# Sheet13.net
KiCad netlist of a schematic drawn in Altium Designer
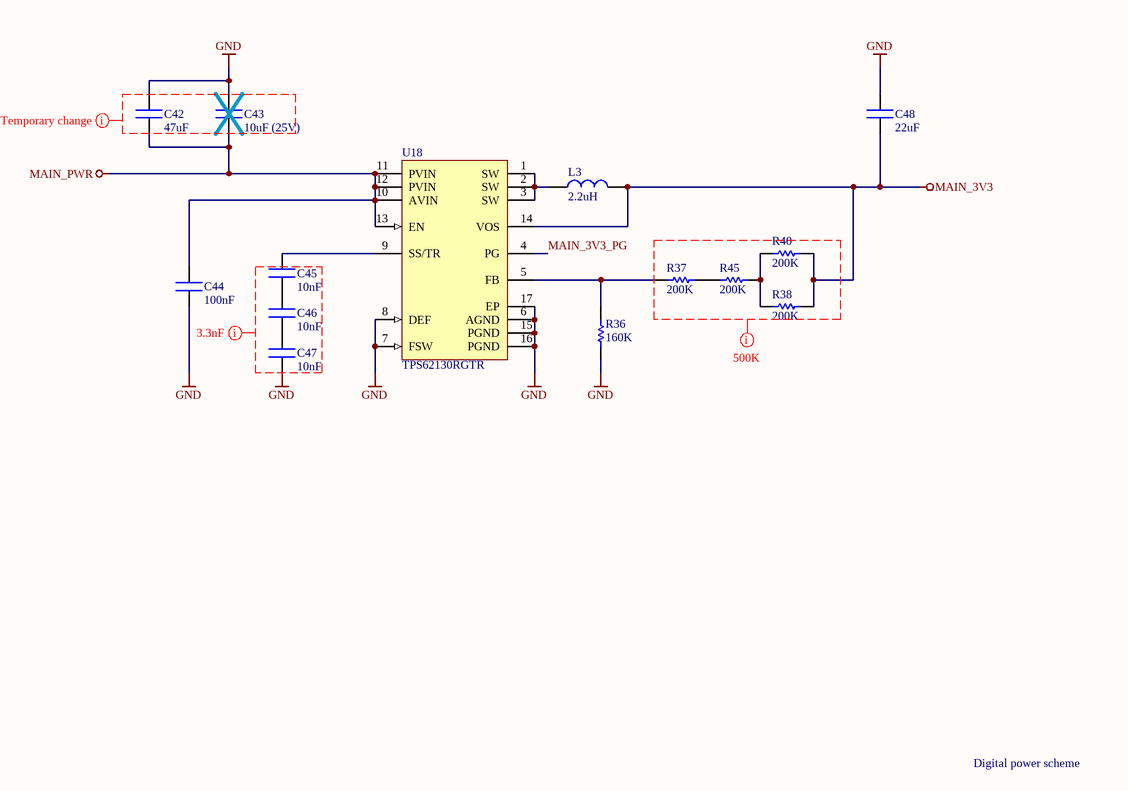
[diagram p0: Sheet13.SchDoc]

(export (version "E")
  (design (tool "Eeschema 10.0.6"))
  (components
    (comp (ref "C42")
      (value "47uF")
      (footprint "CAPC2012X12N")
      (description "Ceramic Chip Capacitor")
      (libsource (lib "Integrated_Library") (part "C0805"))
    )
    (comp (ref "C43")
      (value "10uF (25V)")
      (footprint "CAPC3216X16N")
      (description "Ceramic Chip Capacitor")
      (libsource (lib "Integrated_Library") (part "C1206"))
    )
    (comp (ref "C44")
      (value "100nF")
      (footprint "CAPC1608X08N")
      (description "Ceramic Chip Capacitor")
      (libsource (lib "Integrated_Library") (part "C0603"))
    )
    (comp (ref "C45")
      (value "10nF")
      (footprint "CAPC1005X05N")
      (description "Ceramic Chip Capacitor")
      (libsource (lib "Integrated_Library") (part "C0402"))
    )
    (comp (ref "C46")
      (value "10nF")
      (footprint "CAPC1005X05N")
      (description "Ceramic Chip Capacitor")
      (libsource (lib "Integrated_Library") (part "C0402"))
    )
    (comp (ref "C47")
      (value "10nF")
      (footprint "CAPC1005X05N")
      (description "Ceramic Chip Capacitor")
      (libsource (lib "Integrated_Library") (part "C0402"))
    )
    (comp (ref "C48")
      (value "22uF")
      (footprint "CAPC1608X08N")
      (description "Ceramic Chip Capacitor")
      (libsource (lib "Integrated_Library") (part "C0603"))
    )
    (comp (ref "L3")
      (value "2.2uH")
      (footprint "IHLP1212BZER2R2M11")
      (description "Commercial Inductors, Low DCR Series")
      (libsource (lib "Integrated_Library") (part "IHLP1212BZER2R2M11"))
    )
    (comp (ref "R36")
      (value "160K")
      (footprint "RESC1005X05N")
      (description "Ceramic Chip Resistor")
      (libsource (lib "Integrated_Library") (part "R0402"))
    )
    (comp (ref "R37")
      (value "200K")
      (footprint "RESC1005X05N")
      (description "Ceramic Chip Resistor")
      (libsource (lib "Integrated_Library") (part "R0402"))
    )
    (comp (ref "R38")
      (value "200K")
      (footprint "RESC1005X05N")
      (description "Ceramic Chip Resistor")
      (libsource (lib "Integrated_Library") (part "R0402"))
    )
    (comp (ref "R40")
      (value "200K")
      (footprint "RESC1005X05N")
      (description "Ceramic Chip Resistor")
      (libsource (lib "Integrated_Library") (part "R0402"))
    )
    (comp (ref "R45")
      (value "200K")
      (footprint "RESC1005X05N")
      (description "Ceramic Chip Resistor")
      (libsource (lib "Integrated_Library") (part "R0402"))
    )
    (comp (ref "U18")
      (value "TPS62130RGTR")
      (footprint "TPS62130RGTR")
      (fields (field (name "MANUFACTURER") "Texas Instruments"))
      (libsource (lib "Integrated_Library") (part "TPS62130RGTR"))
    )
  )
  (nets
    (net (code "1") (name "/MAIN_3V3_PG") (class "Default")
      (node (ref "U18") (pin "4") (pinfunction "PG_4") (pintype "tri_state"))
    )
    (net (code "2") (name "GND") (class "Default")
      (node (ref "C42") (pin "2") (pinfunction "2_2") (pintype "passive"))
      (node (ref "C43") (pin "2") (pinfunction "2_2") (pintype "passive"))
      (node (ref "C44") (pin "1") (pinfunction "1_1") (pintype "passive"))
      (node (ref "C47") (pin "1") (pinfunction "1_1") (pintype "passive"))
      (node (ref "C48") (pin "2") (pinfunction "2_2") (pintype "passive"))
      (node (ref "R36") (pin "1") (pinfunction "1_1") (pintype "passive"))
      (node (ref "U18") (pin "15") (pinfunction "PGND_15") (pintype "power_in"))
      (node (ref "U18") (pin "16") (pinfunction "PGND_16") (pintype "power_in"))
      (node (ref "U18") (pin "17") (pinfunction "EP_17") (pintype "power_in"))
      (node (ref "U18") (pin "6") (pinfunction "AGND_6") (pintype "power_in"))
      (node (ref "U18") (pin "7") (pinfunction "FSW_7") (pintype "input"))
      (node (ref "U18") (pin "8") (pinfunction "DEF_8") (pintype "input"))
    )
    (net (code "3") (name "MAIN_3V3") (class "Default")
      (node (ref "C48") (pin "1") (pinfunction "1_1") (pintype "passive"))
      (node (ref "L3") (pin "2") (pinfunction "2_2") (pintype "passive"))
      (node (ref "R38") (pin "2") (pinfunction "2_2") (pintype "passive"))
      (node (ref "R40") (pin "2") (pinfunction "2_2") (pintype "passive"))
      (node (ref "U18") (pin "14") (pinfunction "VOS_14") (pintype "passive"))
    )
    (net (code "4") (name "MAIN_PWR") (class "Default")
      (node (ref "C42") (pin "1") (pinfunction "1_1") (pintype "passive"))
      (node (ref "C43") (pin "1") (pinfunction "1_1") (pintype "passive"))
      (node (ref "C44") (pin "2") (pinfunction "2_2") (pintype "passive"))
      (node (ref "U18") (pin "10") (pinfunction "AVIN_10") (pintype "power_in"))
      (node (ref "U18") (pin "11") (pinfunction "PVIN_11") (pintype "power_in"))
      (node (ref "U18") (pin "12") (pinfunction "PVIN_12") (pintype "power_in"))
      (node (ref "U18") (pin "13") (pinfunction "EN_13") (pintype "input"))
    )
    (net (code "5") (name "Net-(C45-Pad1)") (class "Default")
      (node (ref "C45") (pin "1") (pinfunction "1_1") (pintype "passive"))
      (node (ref "C46") (pin "2") (pinfunction "2_2") (pintype "passive"))
    )
    (net (code "6") (name "Net-(C46-Pad1)") (class "Default")
      (node (ref "C46") (pin "1") (pinfunction "1_1") (pintype "passive"))
      (node (ref "C47") (pin "2") (pinfunction "2_2") (pintype "passive"))
    )
    (net (code "7") (name "Net-(L3-Pad1)") (class "Default")
      (node (ref "L3") (pin "1") (pinfunction "1_1") (pintype "passive"))
      (node (ref "U18") (pin "1") (pinfunction "SW_1") (pintype "power_in"))
      (node (ref "U18") (pin "2") (pinfunction "SW_2") (pintype "power_in"))
      (node (ref "U18") (pin "3") (pinfunction "SW_3") (pintype "power_in"))
    )
    (net (code "8") (name "Net-(R37-Pad1)") (class "Default")
      (node (ref "R37") (pin "1") (pinfunction "1_1") (pintype "passive"))
      (node (ref "R45") (pin "2") (pinfunction "2_2") (pintype "passive"))
    )
    (net (code "9") (name "Net-(R38-Pad1)") (class "Default")
      (node (ref "R38") (pin "1") (pinfunction "1_1") (pintype "passive"))
      (node (ref "R40") (pin "1") (pinfunction "1_1") (pintype "passive"))
      (node (ref "R45") (pin "1") (pinfunction "1_1") (pintype "passive"))
    )
    (net (code "10") (name "Net-(U18-FB)") (class "Default")
      (node (ref "R36") (pin "2") (pinfunction "2_2") (pintype "passive"))
      (node (ref "R37") (pin "2") (pinfunction "2_2") (pintype "passive"))
      (node (ref "U18") (pin "5") (pinfunction "FB_5") (pintype "passive"))
    )
    (net (code "11") (name "Net-(U18-SS{slash}TR)") (class "Default")
      (node (ref "C45") (pin "2") (pinfunction "2_2") (pintype "passive"))
      (node (ref "U18") (pin "9") (pinfunction "SS/TR_9") (pintype "passive"))
    )
  )
)
